# 2_layers_lite.net
KiCad netlist of a schematic drawn in EAGLE
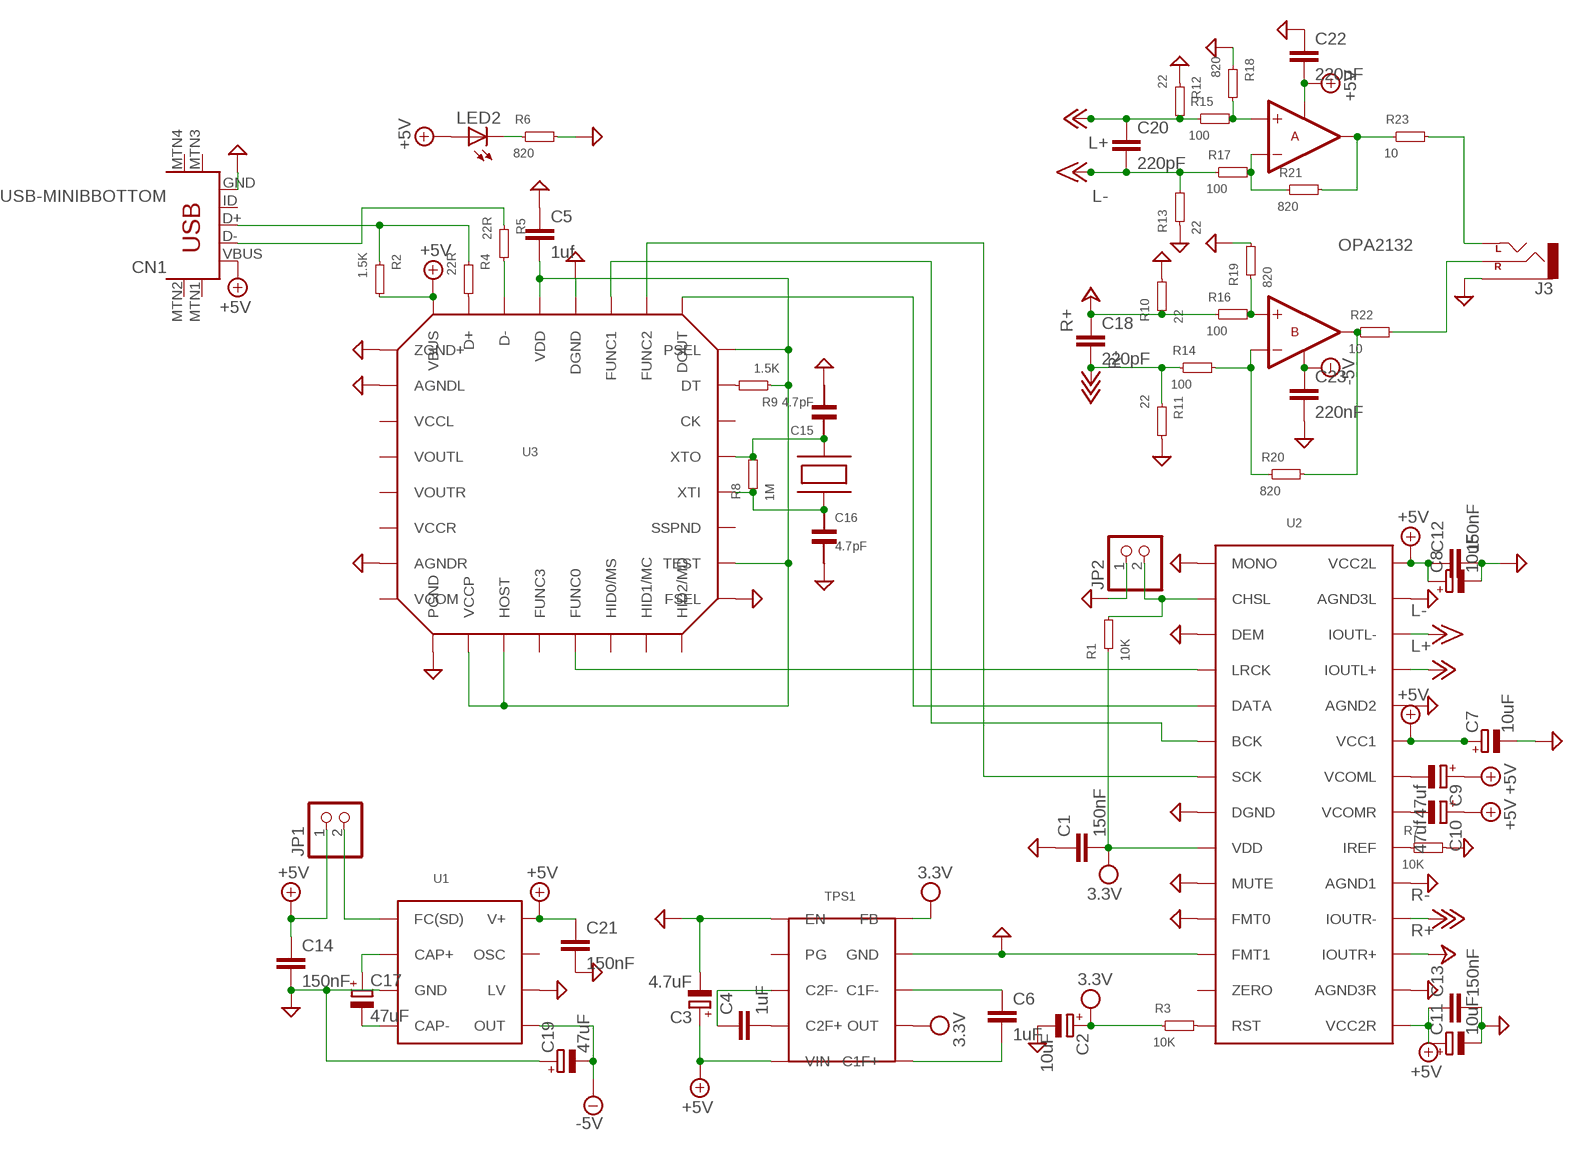
[diagram p0: schematic, sheet 1]

(export (version "E")
  (design (tool "Eeschema 10.0.6"))
  (components
    (comp (ref "C1")
      (value "150nF")
      (footprint "eagle-import:0805")
      (libsource (lib "eagle-import") (part "CAP0805"))
    )
    (comp (ref "C2")
      (value "10uF")
      (footprint "eagle-import:10UF_16V_PANA_M_CAP")
      (libsource (lib "eagle-import") (part "10UF/16V_PANA_M-CAP"))
    )
    (comp (ref "C3")
      (value "4.7uF")
      (footprint "eagle-import:10UF_16V_PANA_M_CAP")
      (libsource (lib "eagle-import") (part "4.7UF/50V_PANA_M-CAP"))
    )
    (comp (ref "C4")
      (value "1uF")
      (footprint "eagle-import:0805")
      (libsource (lib "eagle-import") (part "CAP0805"))
    )
    (comp (ref "C5")
      (value "1uf")
      (footprint "eagle-import:0805")
      (libsource (lib "eagle-import") (part "CAP0805"))
    )
    (comp (ref "C6")
      (value "1uF")
      (footprint "eagle-import:0805")
      (libsource (lib "eagle-import") (part "CAP0805"))
    )
    (comp (ref "C7")
      (value "10uF")
      (footprint "eagle-import:10UF_16V_PANA_M_CAP")
      (libsource (lib "eagle-import") (part "10UF/16V_PANA_M-CAP"))
    )
    (comp (ref "C8")
      (value "10uF")
      (footprint "eagle-import:10UF_16V_PANA_M_CAP")
      (libsource (lib "eagle-import") (part "10UF/16V_PANA_M-CAP"))
    )
    (comp (ref "C9")
      (value "47uf")
      (footprint "eagle-import:10UF_16V_PANA_M_CAP")
      (libsource (lib "eagle-import") (part "47UF/16V_PANA_M-CAP"))
    )
    (comp (ref "C10")
      (value "47uf")
      (footprint "eagle-import:10UF_16V_PANA_M_CAP")
      (libsource (lib "eagle-import") (part "47UF/16V_PANA_M-CAP"))
    )
    (comp (ref "C11")
      (value "10uF")
      (footprint "eagle-import:10UF_16V_PANA_M_CAP")
      (libsource (lib "eagle-import") (part "10UF/16V_PANA_M-CAP"))
    )
    (comp (ref "C12")
      (value "150nF")
      (footprint "eagle-import:0805")
      (libsource (lib "eagle-import") (part "CAP0805"))
    )
    (comp (ref "C13")
      (value "150nF")
      (footprint "eagle-import:0805")
      (libsource (lib "eagle-import") (part "CAP0805"))
    )
    (comp (ref "C14")
      (value "150nF")
      (footprint "eagle-import:0805")
      (libsource (lib "eagle-import") (part "CAP0805"))
    )
    (comp (ref "C15")
      (value "4.7pF")
      (footprint "eagle-import:4.7PF_CAP")
      (libsource (lib "eagle-import") (part "4.7PF_CAPMLCC"))
    )
    (comp (ref "C16")
      (value "4.7pF")
      (footprint "eagle-import:4.7PF_CAP")
      (libsource (lib "eagle-import") (part "4.7PF_CAPMLCC"))
    )
    (comp (ref "C17")
      (value "47uF")
      (footprint "eagle-import:10UF_16V_PANA_M_CAP")
      (libsource (lib "eagle-import") (part "47UF/16V_PANA_M-CAP"))
    )
    (comp (ref "C18")
      (value "220pF")
      (footprint "eagle-import:C050-045X075")
      (libsource (lib "eagle-import") (part "C-EU050-045X075"))
    )
    (comp (ref "C19")
      (value "47uF")
      (footprint "eagle-import:10UF_16V_PANA_M_CAP")
      (libsource (lib "eagle-import") (part "47UF/16V_PANA_M-CAP"))
    )
    (comp (ref "C20")
      (value "220pF")
      (footprint "eagle-import:C050-045X075")
      (libsource (lib "eagle-import") (part "C-EU050-045X075"))
    )
    (comp (ref "C21")
      (value "150nF")
      (footprint "eagle-import:0805")
      (libsource (lib "eagle-import") (part "CAP0805"))
    )
    (comp (ref "C22")
      (value "220nF")
      (footprint "eagle-import:0805")
      (libsource (lib "eagle-import") (part "22UF-6.3V-20%(0805)"))
    )
    (comp (ref "C23")
      (value "220nF")
      (footprint "eagle-import:0805")
      (libsource (lib "eagle-import") (part "22UF-6.3V-20%(0805)"))
    )
    (comp (ref "CN1")
      (value "USB-MINIBBOTTOM")
      (footprint "eagle-import:USB-MINIB")
      (libsource (lib "eagle-import") (part "USB-MINIBBOTTOM"))
    )
    (comp (ref "J3")
      (value "AUDIO-JACKPTH")
      (footprint "eagle-import:AUDIO-JACK")
      (libsource (lib "eagle-import") (part "AUDIO-JACKPTH"))
    )
    (comp (ref "JP1")
      (value "PINHD-1X2")
      (footprint "eagle-import:1X02")
      (libsource (lib "eagle-import") (part "PINHD-1X2"))
    )
    (comp (ref "JP2")
      (value "PINHD-1X2")
      (footprint "eagle-import:1X02")
      (libsource (lib "eagle-import") (part "PINHD-1X2"))
    )
    (comp (ref "LED2")
      (value "LED3MM")
      (footprint "eagle-import:LED3MM")
      (libsource (lib "eagle-import") (part "LED3MM"))
    )
    (comp (ref "OPA2132")
      (value "OPA2132DIP8")
      (footprint "eagle-import:DIP-8")
      (libsource (lib "eagle-import") (part "OPA2132DIP8"))
    )
    (comp (ref "R1")
      (value "10K")
      (footprint "eagle-import:1-8W_RES")
      (libsource (lib "eagle-import") (part "RESISTOR.125W"))
    )
    (comp (ref "R2")
      (value "1.5K")
      (footprint "eagle-import:1-8W_RES")
      (libsource (lib "eagle-import") (part "RESISTOR.125W"))
    )
    (comp (ref "R3")
      (value "10K")
      (footprint "eagle-import:1-8W_RES")
      (libsource (lib "eagle-import") (part "RESISTOR.125W"))
    )
    (comp (ref "R4")
      (value "22R")
      (footprint "eagle-import:1-8W_RES")
      (libsource (lib "eagle-import") (part "RESISTOR.125W"))
    )
    (comp (ref "R5")
      (value "22R")
      (footprint "eagle-import:1-8W_RES")
      (libsource (lib "eagle-import") (part "RESISTOR.125W"))
    )
    (comp (ref "R6")
      (value "820")
      (footprint "eagle-import:1-8W_RES")
      (libsource (lib "eagle-import") (part "RESISTOR.125W"))
    )
    (comp (ref "R7")
      (value "10K")
      (footprint "eagle-import:1-8W_RES")
      (libsource (lib "eagle-import") (part "RESISTOR.125W"))
    )
    (comp (ref "R8")
      (value "1M")
      (footprint "eagle-import:1-8W_RES")
      (libsource (lib "eagle-import") (part "RESISTOR.125W"))
    )
    (comp (ref "R9")
      (value "1.5K")
      (footprint "eagle-import:1-8W_RES")
      (libsource (lib "eagle-import") (part "RESISTOR.125W"))
    )
    (comp (ref "R10")
      (value "22")
      (footprint "eagle-import:1-8W_RES")
      (libsource (lib "eagle-import") (part "RESISTOR.125W"))
    )
    (comp (ref "R11")
      (value "22")
      (footprint "eagle-import:1-8W_RES")
      (libsource (lib "eagle-import") (part "RESISTOR.125W"))
    )
    (comp (ref "R12")
      (value "22")
      (footprint "eagle-import:1-8W_RES")
      (libsource (lib "eagle-import") (part "RESISTOR.125W"))
    )
    (comp (ref "R13")
      (value "22")
      (footprint "eagle-import:1-8W_RES")
      (libsource (lib "eagle-import") (part "RESISTOR.125W"))
    )
    (comp (ref "R14")
      (value "100")
      (footprint "eagle-import:1-8W_RES")
      (libsource (lib "eagle-import") (part "RESISTOR.125W"))
    )
    (comp (ref "R15")
      (value "100")
      (footprint "eagle-import:1-8W_RES")
      (libsource (lib "eagle-import") (part "RESISTOR.125W"))
    )
    (comp (ref "R16")
      (value "100")
      (footprint "eagle-import:1-8W_RES")
      (libsource (lib "eagle-import") (part "RESISTOR.125W"))
    )
    (comp (ref "R17")
      (value "100")
      (footprint "eagle-import:1-8W_RES")
      (libsource (lib "eagle-import") (part "RESISTOR.125W"))
    )
    (comp (ref "R18")
      (value "820")
      (footprint "eagle-import:1-8W_RES")
      (libsource (lib "eagle-import") (part "RESISTOR.125W"))
    )
    (comp (ref "R19")
      (value "820")
      (footprint "eagle-import:1-8W_RES")
      (libsource (lib "eagle-import") (part "RESISTOR.125W"))
    )
    (comp (ref "R20")
      (value "820")
      (footprint "eagle-import:1-8W_RES")
      (libsource (lib "eagle-import") (part "RESISTOR.125W"))
    )
    (comp (ref "R21")
      (value "820")
      (footprint "eagle-import:1-8W_RES")
      (libsource (lib "eagle-import") (part "RESISTOR.125W"))
    )
    (comp (ref "R22")
      (value "10")
      (footprint "eagle-import:1-8W_RES")
      (libsource (lib "eagle-import") (part "RESISTOR.125W"))
    )
    (comp (ref "R23")
      (value "10")
      (footprint "eagle-import:1-8W_RES")
      (libsource (lib "eagle-import") (part "RESISTOR.125W"))
    )
    (comp (ref "TPS1")
      (value "TPS60501DGS-10-BOTTOM")
      (footprint "eagle-import:DGS-10-BOTTOM_LYR")
      (libsource (lib "eagle-import") (part "TPS60501DGS-10-BOTTOM"))
    )
    (comp (ref "U1")
      (value "LM2662SO8-BOTTOM")
      (footprint "eagle-import:SOIC-8_BOTTOM-LYR")
      (libsource (lib "eagle-import") (part "LM2662SO8-BOTTOM"))
    )
    (comp (ref "U2")
      (value "PCM1794ADB_R-PDSO-G28-BOTTOM")
      (footprint "eagle-import:DB_R-PDSO-G28-BOTTOM_LYR")
      (libsource (lib "eagle-import") (part "PCM1794ADB_R-PDSO-G28-BOTTOM"))
    )
    (comp (ref "U3")
      (value "PCM2707QFP-32-BOTTOM")
      (footprint "eagle-import:PJT_(QFP-32)-BOTTOM_LYR")
      (libsource (lib "eagle-import") (part "PCM2707QFP-32-BOTTOM"))
    )
    (comp (ref "X1")
      (value "12MHZ")
      (footprint "eagle-import:CRYSTAL")
      (libsource (lib "eagle-import") (part "CRYSTAL"))
    )
  )
  (nets
    (net (code "1") (name "+5V") (class "Default")
      (node (ref "C10") (pin "+") (pinfunction "+_+") (pintype "passive"))
      (node (ref "C11") (pin "+") (pinfunction "+_+") (pintype "passive"))
      (node (ref "C12") (pin "1") (pinfunction "1_1") (pintype "passive"))
      (node (ref "C13") (pin "1") (pinfunction "1_1") (pintype "passive"))
      (node (ref "C14") (pin "1") (pinfunction "1_1") (pintype "passive"))
      (node (ref "C21") (pin "1") (pinfunction "1_1") (pintype "passive"))
      (node (ref "C22") (pin "2") (pinfunction "2_2") (pintype "passive"))
      (node (ref "C3") (pin "+") (pinfunction "+_+") (pintype "passive"))
      (node (ref "C7") (pin "+") (pinfunction "+_+") (pintype "passive"))
      (node (ref "C8") (pin "+") (pinfunction "+_+") (pintype "passive"))
      (node (ref "C9") (pin "+") (pinfunction "+_+") (pintype "passive"))
      (node (ref "CN1") (pin "VBUS") (pinfunction "VBUS_VBUS") (pintype "bidirectional"))
      (node (ref "JP1") (pin "1") (pinfunction "1_1") (pintype "passive"))
      (node (ref "LED2") (pin "A") (pinfunction "A_A") (pintype "passive"))
      (node (ref "OPA2132") (pin "8") (pinfunction "8(+)_8") (pintype "bidirectional"))
      (node (ref "R2") (pin "P$2") (pinfunction "2_P$2") (pintype "bidirectional"))
      (node (ref "TPS1") (pin "5") (pinfunction "VIN_5") (pintype "bidirectional"))
      (node (ref "U1") (pin "8") (pinfunction "V+_8") (pintype "bidirectional"))
      (node (ref "U2") (pin "15") (pinfunction "VCC2R_15") (pintype "bidirectional"))
      (node (ref "U2") (pin "23") (pinfunction "VCC1_23") (pintype "bidirectional"))
      (node (ref "U2") (pin "28") (pinfunction "VCC2L_28") (pintype "bidirectional"))
      (node (ref "U3") (pin "24") (pinfunction "VBUS_24") (pintype "bidirectional"))
    )
    (net (code "2") (name "-5V") (class "Default")
      (node (ref "C19") (pin "-") (pinfunction "-_-") (pintype "passive"))
      (node (ref "C23") (pin "1") (pinfunction "1_1") (pintype "passive"))
      (node (ref "OPA2132") (pin "4") (pinfunction "4(-)_4") (pintype "bidirectional"))
      (node (ref "U1") (pin "5") (pinfunction "OUT_5") (pintype "bidirectional"))
    )
    (net (code "3") (name "3.3V") (class "Default")
      (node (ref "C1") (pin "2") (pinfunction "2_2") (pintype "passive"))
      (node (ref "C2") (pin "+") (pinfunction "+_+") (pintype "passive"))
      (node (ref "R1") (pin "P$1") (pinfunction "1_P$1") (pintype "bidirectional"))
      (node (ref "R3") (pin "P$1") (pinfunction "1_P$1") (pintype "bidirectional"))
      (node (ref "TPS1") (pin "10") (pinfunction "FB_10") (pintype "bidirectional"))
      (node (ref "TPS1") (pin "7") (pinfunction "OUT_7") (pintype "bidirectional"))
      (node (ref "U2") (pin "9") (pinfunction "VDD_9") (pintype "bidirectional"))
    )
    (net (code "4") (name "GND") (class "Default")
      (node (ref "C1") (pin "1") (pinfunction "1_1") (pintype "passive"))
      (node (ref "C11") (pin "-") (pinfunction "-_-") (pintype "passive"))
      (node (ref "C12") (pin "2") (pinfunction "2_2") (pintype "passive"))
      (node (ref "C13") (pin "2") (pinfunction "2_2") (pintype "passive"))
      (node (ref "C14") (pin "2") (pinfunction "2_2") (pintype "passive"))
      (node (ref "C15") (pin "2") (pinfunction "2_2") (pintype "bidirectional"))
      (node (ref "C16") (pin "2") (pinfunction "2_2") (pintype "bidirectional"))
      (node (ref "C19") (pin "+") (pinfunction "+_+") (pintype "passive"))
      (node (ref "C2") (pin "-") (pinfunction "-_-") (pintype "passive"))
      (node (ref "C21") (pin "2") (pinfunction "2_2") (pintype "passive"))
      (node (ref "C22") (pin "1") (pinfunction "1_1") (pintype "passive"))
      (node (ref "C23") (pin "2") (pinfunction "2_2") (pintype "passive"))
      (node (ref "C3") (pin "-") (pinfunction "-_-") (pintype "passive"))
      (node (ref "C5") (pin "1") (pinfunction "1_1") (pintype "passive"))
      (node (ref "C7") (pin "-") (pinfunction "-_-") (pintype "passive"))
      (node (ref "C8") (pin "-") (pinfunction "-_-") (pintype "passive"))
      (node (ref "CN1") (pin "GND") (pinfunction "GND_GND") (pintype "bidirectional"))
      (node (ref "J3") (pin "SLEEVE") (pinfunction "SLEEVE_SLEEVE") (pintype "bidirectional"))
      (node (ref "JP2") (pin "1") (pinfunction "1_1") (pintype "passive"))
      (node (ref "R10") (pin "P$2") (pinfunction "2_P$2") (pintype "bidirectional"))
      (node (ref "R11") (pin "P$2") (pinfunction "2_P$2") (pintype "bidirectional"))
      (node (ref "R12") (pin "P$1") (pinfunction "1_P$1") (pintype "bidirectional"))
      (node (ref "R13") (pin "P$1") (pinfunction "1_P$1") (pintype "bidirectional"))
      (node (ref "R18") (pin "P$1") (pinfunction "1_P$1") (pintype "bidirectional"))
      (node (ref "R19") (pin "P$2") (pinfunction "2_P$2") (pintype "bidirectional"))
      (node (ref "R6") (pin "P$2") (pinfunction "2_P$2") (pintype "bidirectional"))
      (node (ref "R7") (pin "P$2") (pinfunction "2_P$2") (pintype "bidirectional"))
      (node (ref "TPS1") (pin "1") (pinfunction "EN_1") (pintype "bidirectional"))
      (node (ref "TPS1") (pin "9") (pinfunction "GND_9") (pintype "bidirectional"))
      (node (ref "U1") (pin "3") (pinfunction "GND_3") (pintype "bidirectional"))
      (node (ref "U1") (pin "6") (pinfunction "LV_6") (pintype "bidirectional"))
      (node (ref "U2") (pin "1") (pinfunction "MONO_1") (pintype "bidirectional"))
      (node (ref "U2") (pin "10") (pinfunction "MUTE_10") (pintype "bidirectional"))
      (node (ref "U2") (pin "11") (pinfunction "FMT0_11") (pintype "bidirectional"))
      (node (ref "U2") (pin "12") (pinfunction "FMT1_12") (pintype "bidirectional"))
      (node (ref "U2") (pin "16") (pinfunction "AGND3R_16") (pintype "bidirectional"))
      (node (ref "U2") (pin "19") (pinfunction "AGND1_19") (pintype "bidirectional"))
      (node (ref "U2") (pin "24") (pinfunction "AGND2_24") (pintype "bidirectional"))
      (node (ref "U2") (pin "27") (pinfunction "AGND3L_27") (pintype "bidirectional"))
      (node (ref "U2") (pin "3") (pinfunction "DEM_3") (pintype "bidirectional"))
      (node (ref "U2") (pin "8") (pinfunction "DGND_8") (pintype "bidirectional"))
      (node (ref "U3") (pin "1") (pinfunction "PGND_1") (pintype "bidirectional"))
      (node (ref "U3") (pin "20") (pinfunction "DGND_20") (pintype "bidirectional"))
      (node (ref "U3") (pin "25") (pinfunction "ZGND+_25") (pintype "bidirectional"))
      (node (ref "U3") (pin "26") (pinfunction "AGNDL_26") (pintype "bidirectional"))
      (node (ref "U3") (pin "31") (pinfunction "AGNDR_31") (pintype "bidirectional"))
      (node (ref "U3") (pin "9") (pinfunction "FSEL_9") (pintype "bidirectional"))
    )
    (net (code "5") (name "L+") (class "Default")
      (node (ref "C20") (pin "1") (pinfunction "1_1") (pintype "passive"))
      (node (ref "R12") (pin "P$2") (pinfunction "2_P$2") (pintype "bidirectional"))
      (node (ref "R15") (pin "P$1") (pinfunction "1_P$1") (pintype "bidirectional"))
      (node (ref "U2") (pin "25") (pinfunction "IOUTL+_25") (pintype "bidirectional"))
    )
    (net (code "6") (name "L-") (class "Default")
      (node (ref "C20") (pin "2") (pinfunction "2_2") (pintype "passive"))
      (node (ref "R13") (pin "P$2") (pinfunction "2_P$2") (pintype "bidirectional"))
      (node (ref "R17") (pin "P$1") (pinfunction "1_P$1") (pintype "bidirectional"))
      (node (ref "U2") (pin "26") (pinfunction "IOUTL-_26") (pintype "bidirectional"))
    )
    (net (code "7") (name "Net-(J3-LEFT)") (class "Default")
      (node (ref "J3") (pin "TIP") (pinfunction "LEFT_TIP") (pintype "bidirectional"))
      (node (ref "R23") (pin "P$2") (pinfunction "2_P$2") (pintype "bidirectional"))
    )
    (net (code "8") (name "Net-(J3-RIGHT)") (class "Default")
      (node (ref "J3") (pin "RING") (pinfunction "RIGHT_RING") (pintype "bidirectional"))
      (node (ref "R22") (pin "P$2") (pinfunction "2_P$2") (pintype "bidirectional"))
    )
    (net (code "9") (name "Net-(LED2-C)") (class "Default")
      (node (ref "LED2") (pin "K") (pinfunction "C_K") (pintype "passive"))
      (node (ref "R6") (pin "P$1") (pinfunction "1_P$1") (pintype "bidirectional"))
    )
    (net (code "10") (name "Net-(R1-2)") (class "Default")
      (node (ref "JP2") (pin "2") (pinfunction "2_2") (pintype "passive"))
      (node (ref "R1") (pin "P$2") (pinfunction "2_P$2") (pintype "bidirectional"))
      (node (ref "U2") (pin "2") (pinfunction "CHSL_2") (pintype "bidirectional"))
    )
    (net (code "11") (name "Net-(R2-1)") (class "Default")
      (node (ref "CN1") (pin "D+") (pinfunction "D+_D+") (pintype "bidirectional"))
      (node (ref "R2") (pin "P$1") (pinfunction "1_P$1") (pintype "bidirectional"))
      (node (ref "R4") (pin "P$1") (pinfunction "1_P$1") (pintype "bidirectional"))
    )
    (net (code "12") (name "Net-(R3-2)") (class "Default")
      (node (ref "R3") (pin "P$2") (pinfunction "2_P$2") (pintype "bidirectional"))
      (node (ref "U2") (pin "14") (pinfunction "RST_14") (pintype "bidirectional"))
    )
    (net (code "13") (name "Net-(R4-2)") (class "Default")
      (node (ref "R4") (pin "P$2") (pinfunction "2_P$2") (pintype "bidirectional"))
      (node (ref "U3") (pin "23") (pinfunction "D+_23") (pintype "bidirectional"))
    )
    (net (code "14") (name "Net-(R5-1)") (class "Default")
      (node (ref "CN1") (pin "D-") (pinfunction "D-_D-") (pintype "bidirectional"))
      (node (ref "R5") (pin "P$1") (pinfunction "1_P$1") (pintype "bidirectional"))
    )
    (net (code "15") (name "Net-(R5-2)") (class "Default")
      (node (ref "R5") (pin "P$2") (pinfunction "2_P$2") (pintype "bidirectional"))
      (node (ref "U3") (pin "22") (pinfunction "D-_22") (pintype "bidirectional"))
    )
    (net (code "16") (name "Net-(R7-1)") (class "Default")
      (node (ref "R7") (pin "P$1") (pinfunction "1_P$1") (pintype "bidirectional"))
      (node (ref "U2") (pin "20") (pinfunction "IREF_20") (pintype "bidirectional"))
    )
    (net (code "17") (name "Net-(R8-1)") (class "Default")
      (node (ref "C16") (pin "1") (pinfunction "1_1") (pintype "bidirectional"))
      (node (ref "R8") (pin "P$1") (pinfunction "1_P$1") (pintype "bidirectional"))
      (node (ref "U3") (pin "12") (pinfunction "XTI_12") (pintype "bidirectional"))
      (node (ref "X1") (pin "1") (pinfunction "1_1") (pintype "bidirectional"))
    )
    (net (code "18") (name "Net-(R8-2)") (class "Default")
      (node (ref "C15") (pin "1") (pinfunction "1_1") (pintype "bidirectional"))
      (node (ref "R8") (pin "P$2") (pinfunction "2_P$2") (pintype "bidirectional"))
      (node (ref "U3") (pin "13") (pinfunction "XTO_13") (pintype "bidirectional"))
      (node (ref "X1") (pin "2") (pinfunction "2_2") (pintype "bidirectional"))
    )
    (net (code "19") (name "Net-(R9-1)") (class "Default")
      (node (ref "C5") (pin "2") (pinfunction "2_2") (pintype "passive"))
      (node (ref "R9") (pin "P$1") (pinfunction "1_P$1") (pintype "bidirectional"))
      (node (ref "U3") (pin "10") (pinfunction "TEST_10") (pintype "bidirectional"))
      (node (ref "U3") (pin "16") (pinfunction "PSEL_16") (pintype "bidirectional"))
      (node (ref "U3") (pin "2") (pinfunction "VCCP_2") (pintype "bidirectional"))
      (node (ref "U3") (pin "21") (pinfunction "VDD_21") (pintype "bidirectional"))
      (node (ref "U3") (pin "3") (pinfunction "HOST_3") (pintype "bidirectional"))
    )
    (net (code "20") (name "Net-(R9-2)") (class "Default")
      (node (ref "R9") (pin "P$2") (pinfunction "2_P$2") (pintype "bidirectional"))
      (node (ref "U3") (pin "15") (pinfunction "DT_15") (pintype "bidirectional"))
    )
    (net (code "21") (name "Net-(R14-2)") (class "Default")
      (node (ref "OPA2132") (pin "6") (pinfunction "6_6") (pintype "input"))
      (node (ref "R14") (pin "P$2") (pinfunction "2_P$2") (pintype "bidirectional"))
      (node (ref "R20") (pin "P$1") (pinfunction "1_P$1") (pintype "bidirectional"))
    )
    (net (code "22") (name "Net-(R15-2)") (class "Default")
      (node (ref "OPA2132") (pin "3") (pinfunction "3_3") (pintype "input"))
      (node (ref "R15") (pin "P$2") (pinfunction "2_P$2") (pintype "bidirectional"))
      (node (ref "R18") (pin "P$2") (pinfunction "2_P$2") (pintype "bidirectional"))
    )
    (net (code "23") (name "Net-(R16-2)") (class "Default")
      (node (ref "OPA2132") (pin "5") (pinfunction "5_5") (pintype "input"))
      (node (ref "R16") (pin "P$2") (pinfunction "2_P$2") (pintype "bidirectional"))
      (node (ref "R19") (pin "P$1") (pinfunction "1_P$1") (pintype "bidirectional"))
    )
    (net (code "24") (name "Net-(R17-2)") (class "Default")
      (node (ref "OPA2132") (pin "2") (pinfunction "2_2") (pintype "input"))
      (node (ref "R17") (pin "P$2") (pinfunction "2_P$2") (pintype "bidirectional"))
      (node (ref "R21") (pin "P$1") (pinfunction "1_P$1") (pintype "bidirectional"))
    )
    (net (code "25") (name "Net-(R20-2)") (class "Default")
      (node (ref "OPA2132") (pin "7") (pinfunction "7_7") (pintype "output"))
      (node (ref "R20") (pin "P$2") (pinfunction "2_P$2") (pintype "bidirectional"))
      (node (ref "R22") (pin "P$1") (pinfunction "1_P$1") (pintype "bidirectional"))
    )
    (net (code "26") (name "Net-(R21-2)") (class "Default")
      (node (ref "OPA2132") (pin "1") (pinfunction "1_1") (pintype "output"))
      (node (ref "R21") (pin "P$2") (pinfunction "2_P$2") (pintype "bidirectional"))
      (node (ref "R23") (pin "P$1") (pinfunction "1_P$1") (pintype "bidirectional"))
    )
    (net (code "27") (name "Net-(TPS1-C1F+)") (class "Default")
      (node (ref "C6") (pin "2") (pinfunction "2_2") (pintype "passive"))
      (node (ref "TPS1") (pin "6") (pinfunction "C1F+_6") (pintype "bidirectional"))
    )
    (net (code "28") (name "Net-(TPS1-C1F-)") (class "Default")
      (node (ref "C6") (pin "1") (pinfunction "1_1") (pintype "passive"))
      (node (ref "TPS1") (pin "8") (pinfunction "C1F-_8") (pintype "bidirectional"))
    )
    (net (code "29") (name "Net-(TPS1-C2F+)") (class "Default")
      (node (ref "C4") (pin "2") (pinfunction "2_2") (pintype "passive"))
      (node (ref "TPS1") (pin "4") (pinfunction "C2F+_4") (pintype "bidirectional"))
    )
    (net (code "30") (name "Net-(TPS1-C2F-)") (class "Default")
      (node (ref "C4") (pin "1") (pinfunction "1_1") (pintype "passive"))
      (node (ref "TPS1") (pin "3") (pinfunction "C2F-_3") (pintype "bidirectional"))
    )
    (net (code "31") (name "Net-(U1-CAP+)") (class "Default")
      (node (ref "C17") (pin "+") (pinfunction "+_+") (pintype "passive"))
      (node (ref "U1") (pin "2") (pinfunction "CAP+_2") (pintype "bidirectional"))
    )
    (net (code "32") (name "Net-(U1-CAP-)") (class "Default")
      (node (ref "C17") (pin "-") (pinfunction "-_-") (pintype "passive"))
      (node (ref "U1") (pin "4") (pinfunction "CAP-_4") (pintype "bidirectional"))
    )
    (net (code "33") (name "Net-(U1-FC(SD))") (class "Default")
      (node (ref "JP1") (pin "2") (pinfunction "2_2") (pintype "passive"))
      (node (ref "U1") (pin "1") (pinfunction "FC(SD)_1") (pintype "bidirectional"))
    )
    (net (code "34") (name "Net-(U2-BCK)") (class "Default")
      (node (ref "U2") (pin "6") (pinfunction "BCK_6") (pintype "bidirectional"))
      (node (ref "U3") (pin "19") (pinfunction "FUNC1_19") (pintype "bidirectional"))
    )
    (net (code "35") (name "Net-(U2-DATA)") (class "Default")
      (node (ref "U2") (pin "5") (pinfunction "DATA_5") (pintype "bidirectional"))
      (node (ref "U3") (pin "17") (pinfunction "DOUT_17") (pintype "bidirectional"))
    )
    (net (code "36") (name "Net-(U2-LRCK)") (class "Default")
      (node (ref "U2") (pin "4") (pinfunction "LRCK_4") (pintype "bidirectional"))
      (node (ref "U3") (pin "5") (pinfunction "FUNC0_5") (pintype "bidirectional"))
    )
    (net (code "37") (name "Net-(U2-SCK)") (class "Default")
      (node (ref "U2") (pin "7") (pinfunction "SCK_7") (pintype "bidirectional"))
      (node (ref "U3") (pin "18") (pinfunction "FUNC2_18") (pintype "bidirectional"))
    )
    (net (code "38") (name "Net-(U2-VCOML)") (class "Default")
      (node (ref "C9") (pin "-") (pinfunction "-_-") (pintype "passive"))
      (node (ref "U2") (pin "22") (pinfunction "VCOML_22") (pintype "bidirectional"))
    )
    (net (code "39") (name "Net-(U2-VCOMR)") (class "Default")
      (node (ref "C10") (pin "-") (pinfunction "-_-") (pintype "passive"))
      (node (ref "U2") (pin "21") (pinfunction "VCOMR_21") (pintype "bidirectional"))
    )
    (net (code "40") (name "R+") (class "Default")
      (node (ref "C18") (pin "1") (pinfunction "1_1") (pintype "passive"))
      (node (ref "R10") (pin "P$1") (pinfunction "1_P$1") (pintype "bidirectional"))
      (node (ref "R16") (pin "P$1") (pinfunction "1_P$1") (pintype "bidirectional"))
      (node (ref "U2") (pin "17") (pinfunction "IOUTR+_17") (pintype "bidirectional"))
    )
    (net (code "41") (name "R-") (class "Default")
      (node (ref "C18") (pin "2") (pinfunction "2_2") (pintype "passive"))
      (node (ref "R11") (pin "P$1") (pinfunction "1_P$1") (pintype "bidirectional"))
      (node (ref "R14") (pin "P$1") (pinfunction "1_P$1") (pintype "bidirectional"))
      (node (ref "U2") (pin "18") (pinfunction "IOUTR-_18") (pintype "bidirectional"))
    )
    (net (code "42") (name "unconnected-(CN1-PadID)") (class "Default")
      (node (ref "CN1") (pin "ID") (pinfunction "ID_ID") (pintype "bidirectional"))
    )
    (net (code "43") (name "unconnected-(CN1-PadMTN1)") (class "Default")
      (node (ref "CN1") (pin "MTN1") (pinfunction "MTN1_MTN1") (pintype "bidirectional"))
    )
    (net (code "44") (name "unconnected-(CN1-PadMTN2)") (class "Default")
      (node (ref "CN1") (pin "MTN2") (pinfunction "MTN2_MTN2") (pintype "bidirectional"))
    )
    (net (code "45") (name "unconnected-(CN1-PadMTN3)") (class "Default")
      (node (ref "CN1") (pin "MTN3") (pinfunction "MTN3_MTN3") (pintype "bidirectional"))
    )
    (net (code "46") (name "unconnected-(CN1-PadMTN4)") (class "Default")
      (node (ref "CN1") (pin "MTN4") (pinfunction "MTN4_MTN4") (pintype "bidirectional"))
    )
    (net (code "47") (name "unconnected-(TPS1-PG-Pad2)") (class "Default")
      (node (ref "TPS1") (pin "2") (pinfunction "PG_2") (pintype "bidirectional"))
    )
    (net (code "48") (name "unconnected-(U1-OSC-Pad7)") (class "Default")
      (node (ref "U1") (pin "7") (pinfunction "OSC_7") (pintype "bidirectional"))
    )
    (net (code "49") (name "unconnected-(U2-ZERO-Pad13)") (class "Default")
      (node (ref "U2") (pin "13") (pinfunction "ZERO_13") (pintype "bidirectional"))
    )
    (net (code "50") (name "unconnected-(U3-CK-Pad14)") (class "Default")
      (node (ref "U3") (pin "14") (pinfunction "CK_14") (pintype "bidirectional"))
    )
    (net (code "51") (name "unconnected-(U3-FUNC3-Pad4)") (class "Default")
      (node (ref "U3") (pin "4") (pinfunction "FUNC3_4") (pintype "bidirectional"))
    )
    (net (code "52") (name "unconnected-(U3-HID0{slash}MS-Pad6)") (class "Default")
      (node (ref "U3") (pin "6") (pinfunction "HID0/MS_6") (pintype "bidirectional"))
    )
    (net (code "53") (name "unconnected-(U3-HID1{slash}MC-Pad7)") (class "Default")
      (node (ref "U3") (pin "7") (pinfunction "HID1/MC_7") (pintype "bidirectional"))
    )
    (net (code "54") (name "unconnected-(U3-HID2{slash}MD-Pad8)") (class "Default")
      (node (ref "U3") (pin "8") (pinfunction "HID2/MD_8") (pintype "bidirectional"))
    )
    (net (code "55") (name "unconnected-(U3-SSPND-Pad11)") (class "Default")
      (node (ref "U3") (pin "11") (pinfunction "SSPND_11") (pintype "bidirectional"))
    )
    (net (code "56") (name "unconnected-(U3-VCCL-Pad27)") (class "Default")
      (node (ref "U3") (pin "27") (pinfunction "VCCL_27") (pintype "bidirectional"))
    )
    (net (code "57") (name "unconnected-(U3-VCCR-Pad30)") (class "Default")
      (node (ref "U3") (pin "30") (pinfunction "VCCR_30") (pintype "bidirectional"))
    )
    (net (code "58") (name "unconnected-(U3-VCOM-Pad32)") (class "Default")
      (node (ref "U3") (pin "32") (pinfunction "VCOM_32") (pintype "bidirectional"))
    )
    (net (code "59") (name "unconnected-(U3-VOUTL-Pad28)") (class "Default")
      (node (ref "U3") (pin "28") (pinfunction "VOUTL_28") (pintype "bidirectional"))
    )
    (net (code "60") (name "unconnected-(U3-VOUTR-Pad29)") (class "Default")
      (node (ref "U3") (pin "29") (pinfunction "VOUTR_29") (pintype "bidirectional"))
    )
  )
)
